# schematic_1_nanang.net
KiCad netlist of a schematic drawn in EAGLE
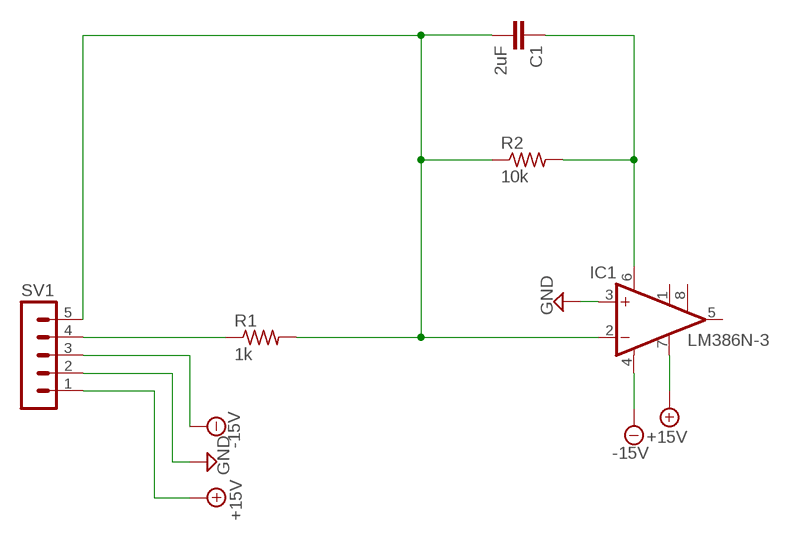
[diagram p0: schematic, sheet 1]

(export (version "E")
  (design (tool "Eeschema 10.0.6"))
  (components
    (comp (ref "C1")
      (value "2uF")
      (footprint "eagle-import:C2.5-3")
      (libsource (lib "eagle-import") (part "C2,5-3"))
    )
    (comp (ref "IC1")
      (value "LM386N-3")
      (footprint "eagle-import:DIL08")
      (libsource (lib "eagle-import") (part "LM386?-N3"))
    )
    (comp (ref "R1")
      (value "1k")
      (footprint "eagle-import:0204_7")
      (libsource (lib "eagle-import") (part "R-US_0204/7"))
    )
    (comp (ref "R2")
      (value "10k")
      (footprint "eagle-import:0204_7")
      (libsource (lib "eagle-import") (part "R-US_0204/7"))
    )
    (comp (ref "SV1")
      (value "MA05-1")
      (footprint "eagle-import:MA05-1")
      (libsource (lib "eagle-import") (part "MA05-1"))
    )
  )
  (nets
    (net (code "1") (name "+15V") (class "Default")
      (node (ref "IC1") (pin "7") (pinfunction "BYPASS_7") (pintype "passive"))
      (node (ref "SV1") (pin "1") (pinfunction "1_1") (pintype "passive"))
    )
    (net (code "2") (name "-15V") (class "Default")
      (node (ref "IC1") (pin "4") (pinfunction "GND_4") (pintype "power_in"))
      (node (ref "SV1") (pin "3") (pinfunction "3_3") (pintype "passive"))
    )
    (net (code "3") (name "GND") (class "Default")
      (node (ref "IC1") (pin "3") (pinfunction "+IN_3") (pintype "input"))
      (node (ref "SV1") (pin "2") (pinfunction "2_2") (pintype "passive"))
    )
    (net (code "4") (name "Net-(IC1--IN)") (class "Default")
      (node (ref "C1") (pin "2") (pinfunction "2_2") (pintype "passive"))
      (node (ref "IC1") (pin "2") (pinfunction "-IN_2") (pintype "input"))
      (node (ref "R1") (pin "2") (pinfunction "2_2") (pintype "passive"))
      (node (ref "R2") (pin "1") (pinfunction "1_1") (pintype "passive"))
      (node (ref "SV1") (pin "5") (pinfunction "5_5") (pintype "passive"))
    )
    (net (code "5") (name "Net-(IC1-VS)") (class "Default")
      (node (ref "C1") (pin "1") (pinfunction "1_1") (pintype "passive"))
      (node (ref "IC1") (pin "6") (pinfunction "VS_6") (pintype "power_in"))
      (node (ref "R2") (pin "2") (pinfunction "2_2") (pintype "passive"))
    )
    (net (code "6") (name "Net-(R1-Pad1)") (class "Default")
      (node (ref "R1") (pin "1") (pinfunction "1_1") (pintype "passive"))
      (node (ref "SV1") (pin "4") (pinfunction "4_4") (pintype "passive"))
    )
    (net (code "7") (name "unconnected-(IC1-GAIN-Pad1)") (class "Default")
      (node (ref "IC1") (pin "1") (pinfunction "GAIN_1") (pintype "passive"))
    )
    (net (code "8") (name "unconnected-(IC1-GAIN-Pad8)") (class "Default")
      (node (ref "IC1") (pin "8") (pinfunction "GAIN_8") (pintype "passive"))
    )
    (net (code "9") (name "unconnected-(IC1-OUT-Pad5)") (class "Default")
      (node (ref "IC1") (pin "5") (pinfunction "OUT_5") (pintype "output"))
    )
  )
)
